# BattleBits_V4.net
KiCad netlist of a schematic drawn in EAGLE
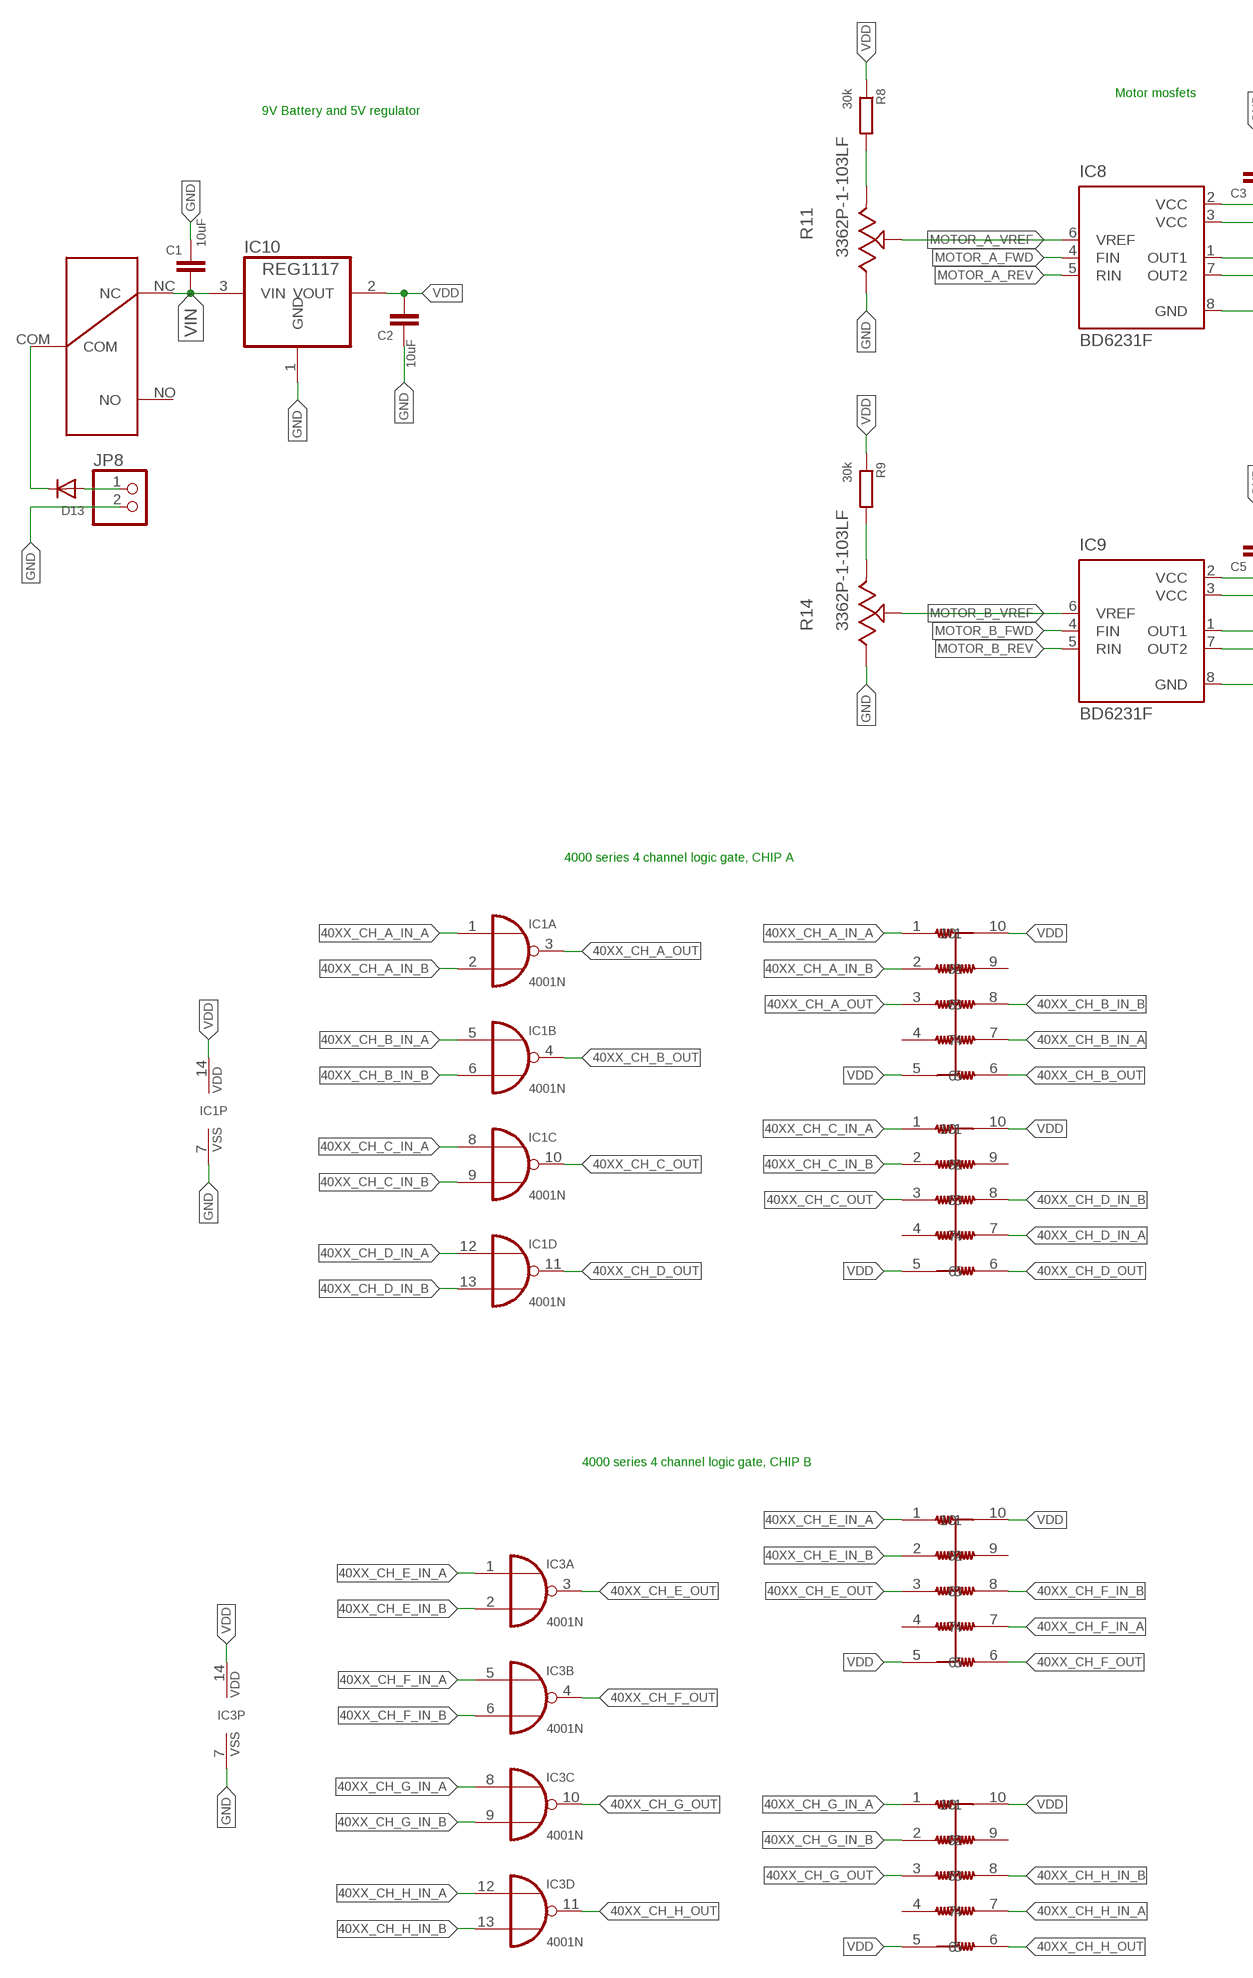
[diagram p0: schematic, sheet 1, part 1 of 2]
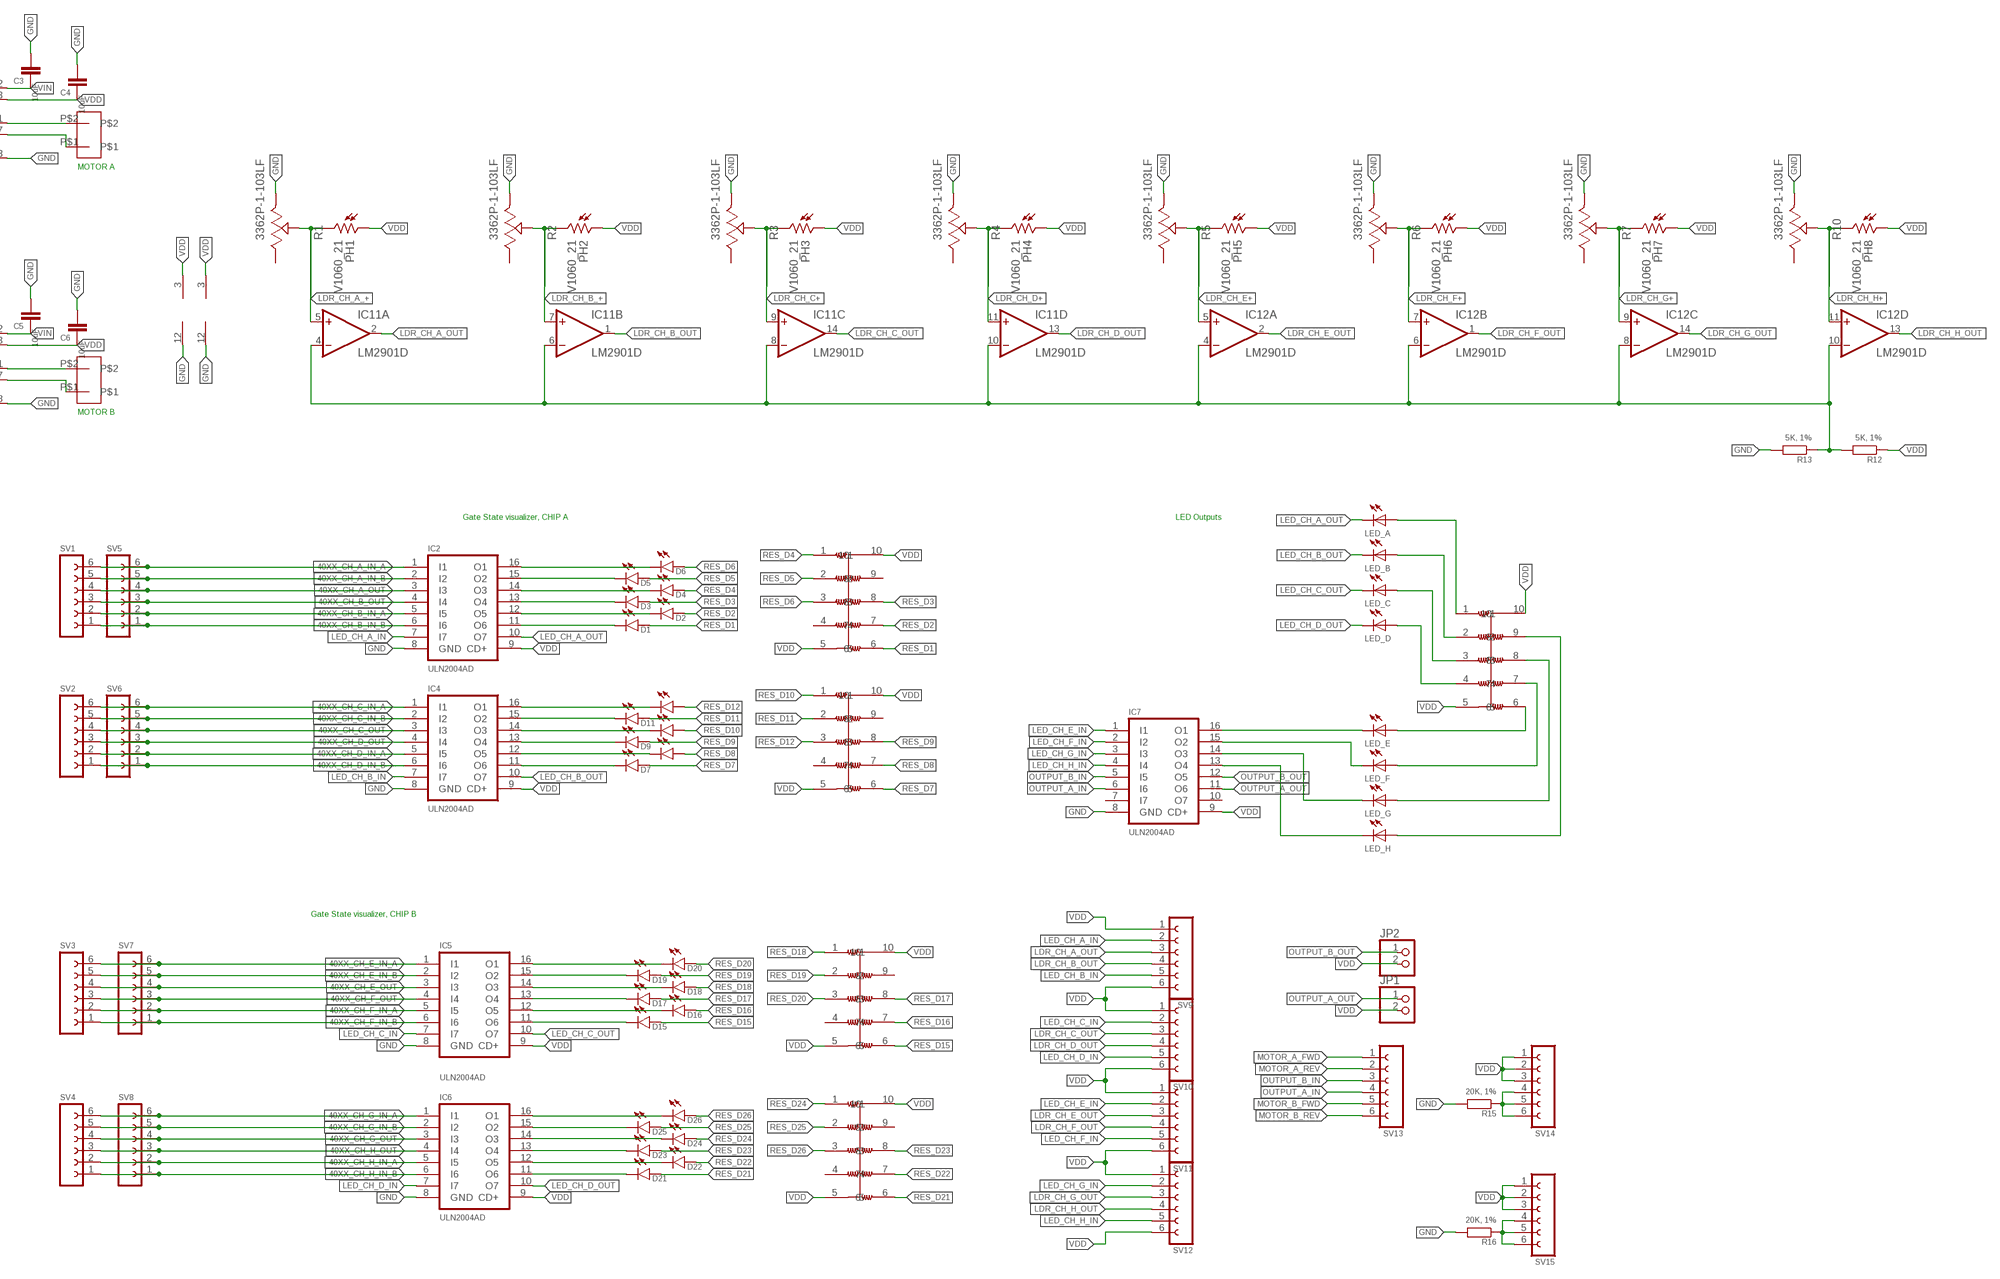
[diagram p1: schematic, sheet 1, part 2 of 2]

(export (version "E")
  (design (tool "Eeschema 10.0.6"))
  (components
    (comp (ref "C1")
      (value "10uF")
      (footprint "eagle-import:C3216")
      (libsource (lib "eagle-import") (part "C-EUC3216"))
    )
    (comp (ref "C2")
      (value "10uF")
      (footprint "eagle-import:C3216")
      (libsource (lib "eagle-import") (part "C-EUC3216"))
    )
    (comp (ref "C3")
      (value "10uF")
      (footprint "eagle-import:C3216")
      (libsource (lib "eagle-import") (part "C-EUC3216"))
    )
    (comp (ref "C4")
      (value "10uF")
      (footprint "eagle-import:C3216")
      (libsource (lib "eagle-import") (part "C-EUC3216"))
    )
    (comp (ref "C5")
      (value "10uF")
      (footprint "eagle-import:C3216")
      (libsource (lib "eagle-import") (part "C-EUC3216"))
    )
    (comp (ref "C6")
      (value "10uF")
      (footprint "eagle-import:C3216")
      (libsource (lib "eagle-import") (part "C-EUC3216"))
    )
    (comp (ref "D1")
      (value "LED1206")
      (footprint "eagle-import:LED-1206")
      (libsource (lib "eagle-import") (part "LED1206"))
    )
    (comp (ref "D2")
      (value "LED1206")
      (footprint "eagle-import:LED-1206")
      (libsource (lib "eagle-import") (part "LED1206"))
    )
    (comp (ref "D3")
      (value "LED1206")
      (footprint "eagle-import:LED-1206")
      (libsource (lib "eagle-import") (part "LED1206"))
    )
    (comp (ref "D4")
      (value "LED1206")
      (footprint "eagle-import:LED-1206")
      (libsource (lib "eagle-import") (part "LED1206"))
    )
    (comp (ref "D5")
      (value "LED1206")
      (footprint "eagle-import:LED-1206")
      (libsource (lib "eagle-import") (part "LED1206"))
    )
    (comp (ref "D6")
      (value "LED1206")
      (footprint "eagle-import:LED-1206")
      (libsource (lib "eagle-import") (part "LED1206"))
    )
    (comp (ref "D7")
      (value "LED1206")
      (footprint "eagle-import:LED-1206")
      (libsource (lib "eagle-import") (part "LED1206"))
    )
    (comp (ref "D8")
      (value "LED1206")
      (footprint "eagle-import:LED-1206")
      (libsource (lib "eagle-import") (part "LED1206"))
    )
    (comp (ref "D9")
      (value "LED1206")
      (footprint "eagle-import:LED-1206")
      (libsource (lib "eagle-import") (part "LED1206"))
    )
    (comp (ref "D10")
      (value "LED1206")
      (footprint "eagle-import:LED-1206")
      (libsource (lib "eagle-import") (part "LED1206"))
    )
    (comp (ref "D11")
      (value "LED1206")
      (footprint "eagle-import:LED-1206")
      (libsource (lib "eagle-import") (part "LED1206"))
    )
    (comp (ref "D12")
      (value "LED1206")
      (footprint "eagle-import:LED-1206")
      (libsource (lib "eagle-import") (part "LED1206"))
    )
    (comp (ref "D13")
      (value "DIODESMA")
      (footprint "eagle-import:SMADIODE")
      (libsource (lib "eagle-import") (part "DIODESMA"))
    )
    (comp (ref "D15")
      (value "LED1206")
      (footprint "eagle-import:LED-1206")
      (libsource (lib "eagle-import") (part "LED1206"))
    )
    (comp (ref "D16")
      (value "LED1206")
      (footprint "eagle-import:LED-1206")
      (libsource (lib "eagle-import") (part "LED1206"))
    )
    (comp (ref "D17")
      (value "LED1206")
      (footprint "eagle-import:LED-1206")
      (libsource (lib "eagle-import") (part "LED1206"))
    )
    (comp (ref "D18")
      (value "LED1206")
      (footprint "eagle-import:LED-1206")
      (libsource (lib "eagle-import") (part "LED1206"))
    )
    (comp (ref "D19")
      (value "LED1206")
      (footprint "eagle-import:LED-1206")
      (libsource (lib "eagle-import") (part "LED1206"))
    )
    (comp (ref "D20")
      (value "LED1206")
      (footprint "eagle-import:LED-1206")
      (libsource (lib "eagle-import") (part "LED1206"))
    )
    (comp (ref "D21")
      (value "LED1206")
      (footprint "eagle-import:LED-1206")
      (libsource (lib "eagle-import") (part "LED1206"))
    )
    (comp (ref "D22")
      (value "LED1206")
      (footprint "eagle-import:LED-1206")
      (libsource (lib "eagle-import") (part "LED1206"))
    )
    (comp (ref "D23")
      (value "LED1206")
      (footprint "eagle-import:LED-1206")
      (libsource (lib "eagle-import") (part "LED1206"))
    )
    (comp (ref "D24")
      (value "LED1206")
      (footprint "eagle-import:LED-1206")
      (libsource (lib "eagle-import") (part "LED1206"))
    )
    (comp (ref "D25")
      (value "LED1206")
      (footprint "eagle-import:LED-1206")
      (libsource (lib "eagle-import") (part "LED1206"))
    )
    (comp (ref "D26")
      (value "LED1206")
      (footprint "eagle-import:LED-1206")
      (libsource (lib "eagle-import") (part "LED1206"))
    )
    (comp (ref "IC1")
      (value "4001N")
      (footprint "eagle-import:DIL14")
      (libsource (lib "eagle-import") (part "4001N"))
    )
    (comp (ref "IC2")
      (value "ULN2004AD")
      (footprint "eagle-import:SO16")
      (libsource (lib "eagle-import") (part "ULN2004AD"))
    )
    (comp (ref "IC3")
      (value "4001N")
      (footprint "eagle-import:DIL14")
      (libsource (lib "eagle-import") (part "4001N"))
    )
    (comp (ref "IC4")
      (value "ULN2004AD")
      (footprint "eagle-import:SO16")
      (libsource (lib "eagle-import") (part "ULN2004AD"))
    )
    (comp (ref "IC5")
      (value "ULN2004AD")
      (footprint "eagle-import:SO16")
      (libsource (lib "eagle-import") (part "ULN2004AD"))
    )
    (comp (ref "IC6")
      (value "ULN2004AD")
      (footprint "eagle-import:SO16")
      (libsource (lib "eagle-import") (part "ULN2004AD"))
    )
    (comp (ref "IC7")
      (value "ULN2004AD")
      (footprint "eagle-import:SO16")
      (libsource (lib "eagle-import") (part "ULN2004AD"))
    )
    (comp (ref "IC8")
      (value "BD6231F")
      (footprint "eagle-import:SOP8")
      (fields (field (name "MPN") "BD6231F-E2"))
      (libsource (lib "eagle-import") (part "BD623F1"))
    )
    (comp (ref "IC9")
      (value "BD6231F")
      (footprint "eagle-import:SOP8")
      (fields (field (name "MPN") "BD6231F-E2"))
      (libsource (lib "eagle-import") (part "BD623F1"))
    )
    (comp (ref "IC10")
      (value "REG1117")
      (footprint "eagle-import:SOT223")
      (libsource (lib "eagle-import") (part "REG1117"))
    )
    (comp (ref "IC11")
      (value "LM2901D")
      (footprint "eagle-import:SO14")
      (libsource (lib "eagle-import") (part "LM2901D"))
    )
    (comp (ref "IC12")
      (value "LM2901D")
      (footprint "eagle-import:SO14")
      (libsource (lib "eagle-import") (part "LM2901D"))
    )
    (comp (ref "JP1")
      (value "PINHD-1X2")
      (footprint "eagle-import:1X02")
      (libsource (lib "eagle-import") (part "PINHD-1X2"))
    )
    (comp (ref "JP2")
      (value "PINHD-1X2")
      (footprint "eagle-import:1X02")
      (libsource (lib "eagle-import") (part "PINHD-1X2"))
    )
    (comp (ref "JP8")
      (value "PINHD-1X2")
      (footprint "eagle-import:1X02")
      (libsource (lib "eagle-import") (part "PINHD-1X2"))
    )
    (comp (ref "LED_A")
      (value "LED5MM")
      (footprint "eagle-import:LED5MM")
      (libsource (lib "eagle-import") (part "adafruit_420_LED5MM"))
    )
    (comp (ref "LED_B")
      (value "LED5MM")
      (footprint "eagle-import:LED5MM")
      (libsource (lib "eagle-import") (part "adafruit_420_LED5MM"))
    )
    (comp (ref "LED_C")
      (value "LED5MM")
      (footprint "eagle-import:LED5MM")
      (libsource (lib "eagle-import") (part "adafruit_420_LED5MM"))
    )
    (comp (ref "LED_D")
      (value "LED5MM")
      (footprint "eagle-import:LED5MM")
      (libsource (lib "eagle-import") (part "adafruit_420_LED5MM"))
    )
    (comp (ref "LED_E")
      (value "LED5MM")
      (footprint "eagle-import:LED5MM")
      (libsource (lib "eagle-import") (part "adafruit_420_LED5MM"))
    )
    (comp (ref "LED_F")
      (value "LED5MM")
      (footprint "eagle-import:LED5MM")
      (libsource (lib "eagle-import") (part "adafruit_420_LED5MM"))
    )
    (comp (ref "LED_G")
      (value "LED5MM")
      (footprint "eagle-import:LED5MM")
      (libsource (lib "eagle-import") (part "adafruit_420_LED5MM"))
    )
    (comp (ref "LED_H")
      (value "LED5MM")
      (footprint "eagle-import:LED5MM")
      (libsource (lib "eagle-import") (part "adafruit_420_LED5MM"))
    )
    (comp (ref "PH1")
      (value "V1060_21")
      (footprint "eagle-import:TO-5_V10")
      (libsource (lib "eagle-import") (part "?1060V_21"))
    )
    (comp (ref "PH2")
      (value "V1060_21")
      (footprint "eagle-import:TO-5_V10")
      (libsource (lib "eagle-import") (part "?1060V_21"))
    )
    (comp (ref "PH3")
      (value "V1060_21")
      (footprint "eagle-import:TO-5_V10")
      (libsource (lib "eagle-import") (part "?1060V_21"))
    )
    (comp (ref "PH4")
      (value "V1060_21")
      (footprint "eagle-import:TO-5_V10")
      (libsource (lib "eagle-import") (part "?1060V_21"))
    )
    (comp (ref "PH5")
      (value "V1060_21")
      (footprint "eagle-import:TO-5_V10")
      (libsource (lib "eagle-import") (part "?1060V_21"))
    )
    (comp (ref "PH6")
      (value "V1060_21")
      (footprint "eagle-import:TO-5_V10")
      (libsource (lib "eagle-import") (part "?1060V_21"))
    )
    (comp (ref "PH7")
      (value "V1060_21")
      (footprint "eagle-import:TO-5_V10")
      (libsource (lib "eagle-import") (part "?1060V_21"))
    )
    (comp (ref "PH8")
      (value "V1060_21")
      (footprint "eagle-import:TO-5_V10")
      (libsource (lib "eagle-import") (part "?1060V_21"))
    )
    (comp (ref "R1")
      (value "3362P-1-103LF")
      (footprint "eagle-import:3362P-1-103LF")
      (fields (field (name "MANUFACTURER") "Bourns Inc.") (field (name "CREATED_PN") "PCBLayout.com"))
      (libsource (lib "eagle-import") (part "3362P-1-103LF"))
    )
    (comp (ref "R2")
      (value "3362P-1-103LF")
      (footprint "eagle-import:3362P-1-103LF")
      (fields (field (name "MANUFACTURER") "Bourns Inc.") (field (name "CREATED_PN") "PCBLayout.com"))
      (libsource (lib "eagle-import") (part "3362P-1-103LF"))
    )
    (comp (ref "R3")
      (value "3362P-1-103LF")
      (footprint "eagle-import:3362P-1-103LF")
      (fields (field (name "MANUFACTURER") "Bourns Inc.") (field (name "CREATED_PN") "PCBLayout.com"))
      (libsource (lib "eagle-import") (part "3362P-1-103LF"))
    )
    (comp (ref "R4")
      (value "3362P-1-103LF")
      (footprint "eagle-import:3362P-1-103LF")
      (fields (field (name "MANUFACTURER") "Bourns Inc.") (field (name "CREATED_PN") "PCBLayout.com"))
      (libsource (lib "eagle-import") (part "3362P-1-103LF"))
    )
    (comp (ref "R5")
      (value "3362P-1-103LF")
      (footprint "eagle-import:3362P-1-103LF")
      (fields (field (name "MANUFACTURER") "Bourns Inc.") (field (name "CREATED_PN") "PCBLayout.com"))
      (libsource (lib "eagle-import") (part "3362P-1-103LF"))
    )
    (comp (ref "R6")
      (value "3362P-1-103LF")
      (footprint "eagle-import:3362P-1-103LF")
      (fields (field (name "MANUFACTURER") "Bourns Inc.") (field (name "CREATED_PN") "PCBLayout.com"))
      (libsource (lib "eagle-import") (part "3362P-1-103LF"))
    )
    (comp (ref "R7")
      (value "3362P-1-103LF")
      (footprint "eagle-import:3362P-1-103LF")
      (fields (field (name "MANUFACTURER") "Bourns Inc.") (field (name "CREATED_PN") "PCBLayout.com"))
      (libsource (lib "eagle-import") (part "3362P-1-103LF"))
    )
    (comp (ref "R8")
      (value "30k")
      (footprint "eagle-import:R3216")
      (libsource (lib "eagle-import") (part "R-EU_R3216"))
    )
    (comp (ref "R9")
      (value "30k")
      (footprint "eagle-import:R3216")
      (libsource (lib "eagle-import") (part "R-EU_R3216"))
    )
    (comp (ref "R10")
      (value "3362P-1-103LF")
      (footprint "eagle-import:3362P-1-103LF")
      (fields (field (name "MANUFACTURER") "Bourns Inc.") (field (name "CREATED_PN") "PCBLayout.com"))
      (libsource (lib "eagle-import") (part "3362P-1-103LF"))
    )
    (comp (ref "R11")
      (value "3362P-1-103LF")
      (footprint "eagle-import:3362P-1-103LF")
      (fields (field (name "MANUFACTURER") "Bourns Inc.") (field (name "CREATED_PN") "PCBLayout.com"))
      (libsource (lib "eagle-import") (part "3362P-1-103LF"))
    )
    (comp (ref "R12")
      (value "5K, 1%")
      (footprint "eagle-import:R3216")
      (libsource (lib "eagle-import") (part "R-EU_R3216"))
    )
    (comp (ref "R13")
      (value "5K, 1%")
      (footprint "eagle-import:R3216")
      (libsource (lib "eagle-import") (part "R-EU_R3216"))
    )
    (comp (ref "R14")
      (value "3362P-1-103LF")
      (footprint "eagle-import:3362P-1-103LF")
      (fields (field (name "MANUFACTURER") "Bourns Inc.") (field (name "CREATED_PN") "PCBLayout.com"))
      (libsource (lib "eagle-import") (part "3362P-1-103LF"))
    )
    (comp (ref "R15")
      (value "20K, 1%")
      (footprint "eagle-import:R3216")
      (libsource (lib "eagle-import") (part "R-EU_R3216"))
    )
    (comp (ref "R16")
      (value "20K, 1%")
      (footprint "eagle-import:R3216")
      (libsource (lib "eagle-import") (part "R-EU_R3216"))
    )
    (comp (ref "SV1")
      (value "FE06-1")
      (footprint "eagle-import:FE06")
      (libsource (lib "eagle-import") (part "FE06-1"))
    )
    (comp (ref "SV2")
      (value "FE06-1")
      (footprint "eagle-import:FE06")
      (libsource (lib "eagle-import") (part "FE06-1"))
    )
    (comp (ref "SV3")
      (value "FE06-1")
      (footprint "eagle-import:FE06")
      (libsource (lib "eagle-import") (part "FE06-1"))
    )
    (comp (ref "SV4")
      (value "FE06-1")
      (footprint "eagle-import:FE06")
      (libsource (lib "eagle-import") (part "FE06-1"))
    )
    (comp (ref "SV5")
      (value "FE06-1")
      (footprint "eagle-import:FE06")
      (libsource (lib "eagle-import") (part "FE06-1"))
    )
    (comp (ref "SV6")
      (value "FE06-1")
      (footprint "eagle-import:FE06")
      (libsource (lib "eagle-import") (part "FE06-1"))
    )
    (comp (ref "SV7")
      (value "FE06-1")
      (footprint "eagle-import:FE06")
      (libsource (lib "eagle-import") (part "FE06-1"))
    )
    (comp (ref "SV8")
      (value "FE06-1")
      (footprint "eagle-import:FE06")
      (libsource (lib "eagle-import") (part "FE06-1"))
    )
    (comp (ref "SV9")
      (value "FE06-1")
      (footprint "eagle-import:FE06")
      (libsource (lib "eagle-import") (part "FE06-1"))
    )
    (comp (ref "SV10")
      (value "FE06-1")
      (footprint "eagle-import:FE06")
      (libsource (lib "eagle-import") (part "FE06-1"))
    )
    (comp (ref "SV11")
      (value "FE06-1")
      (footprint "eagle-import:FE06")
      (libsource (lib "eagle-import") (part "FE06-1"))
    )
    (comp (ref "SV12")
      (value "FE06-1")
      (footprint "eagle-import:FE06")
      (libsource (lib "eagle-import") (part "FE06-1"))
    )
    (comp (ref "SV13")
      (value "FE06-1")
      (footprint "eagle-import:FE06")
      (libsource (lib "eagle-import") (part "FE06-1"))
    )
    (comp (ref "SV14")
      (value "FE06-1")
      (footprint "eagle-import:FE06")
      (libsource (lib "eagle-import") (part "FE06-1"))
    )
    (comp (ref "SV15")
      (value "FE06-1")
      (footprint "eagle-import:FE06")
      (libsource (lib "eagle-import") (part "FE06-1"))
    )
    (comp (ref "U$1")
      (value "MOTOR")
      (footprint "eagle-import:GEARMOTOR")
      (libsource (lib "eagle-import") (part "MOTOR"))
    )
    (comp (ref "U$2")
      (value "MOTOR")
      (footprint "eagle-import:GEARMOTOR")
      (libsource (lib "eagle-import") (part "MOTOR"))
    )
    (comp (ref "U$3")
      (value "10K")
      (footprint "eagle-import:EXBA")
      (libsource (lib "eagle-import") (part "EXBA_10P"))
    )
    (comp (ref "U$4")
      (value "330")
      (footprint "eagle-import:EXBA")
      (libsource (lib "eagle-import") (part "EXBA_10P"))
    )
    (comp (ref "U$5")
      (value "10K")
      (footprint "eagle-import:EXBA")
      (libsource (lib "eagle-import") (part "EXBA_10P"))
    )
    (comp (ref "U$6")
      (value "10K")
      (footprint "eagle-import:EXBA")
      (libsource (lib "eagle-import") (part "EXBA_10P"))
    )
    (comp (ref "U$7")
      (value "SLIDE_SWITCH")
      (footprint "eagle-import:SLIDE_SWITCH")
      (libsource (lib "eagle-import") (part "SLIDE_SWITCH"))
    )
    (comp (ref "U$9")
      (value "10K")
      (footprint "eagle-import:EXBA")
      (libsource (lib "eagle-import") (part "EXBA_10P"))
    )
    (comp (ref "U$10")
      (value "10K")
      (footprint "eagle-import:EXBA")
      (libsource (lib "eagle-import") (part "EXBA_10P"))
    )
    (comp (ref "U$11")
      (value "10K")
      (footprint "eagle-import:EXBA")
      (libsource (lib "eagle-import") (part "EXBA_10P"))
    )
    (comp (ref "U$19")
      (value "10K")
      (footprint "eagle-import:EXBA")
      (libsource (lib "eagle-import") (part "EXBA_10P"))
    )
    (comp (ref "U$20")
      (value "10K")
      (footprint "eagle-import:EXBA")
      (libsource (lib "eagle-import") (part "EXBA_10P"))
    )
  )
  (nets
    (net (code "1") (name "40XX_CH_A_IN_A") (class "Default")
      (node (ref "IC1") (pin "1") (pinfunction "I0_1") (pintype "input"))
      (node (ref "IC2") (pin "1") (pinfunction "I1_1") (pintype "input"))
      (node (ref "SV1") (pin "6") (pinfunction "6_6") (pintype "passive"))
      (node (ref "SV5") (pin "6") (pinfunction "6_6") (pintype "passive"))
      (node (ref "U$3") (pin "1") (pinfunction "1_1") (pintype "bidirectional"))
    )
    (net (code "2") (name "40XX_CH_A_IN_B") (class "Default")
      (node (ref "IC1") (pin "2") (pinfunction "I1_2") (pintype "input"))
      (node (ref "IC2") (pin "2") (pinfunction "I2_2") (pintype "input"))
      (node (ref "SV1") (pin "5") (pinfunction "5_5") (pintype "passive"))
      (node (ref "SV5") (pin "5") (pinfunction "5_5") (pintype "passive"))
      (node (ref "U$3") (pin "2") (pinfunction "2_2") (pintype "bidirectional"))
    )
    (net (code "3") (name "40XX_CH_A_OUT") (class "Default")
      (node (ref "IC1") (pin "3") (pinfunction "O_3") (pintype "output"))
      (node (ref "IC2") (pin "3") (pinfunction "I3_3") (pintype "input"))
      (node (ref "SV1") (pin "4") (pinfunction "4_4") (pintype "passive"))
      (node (ref "SV5") (pin "4") (pinfunction "4_4") (pintype "passive"))
      (node (ref "U$3") (pin "3") (pinfunction "3_3") (pintype "bidirectional"))
    )
    (net (code "4") (name "40XX_CH_B_IN_A") (class "Default")
      (node (ref "IC1") (pin "5") (pinfunction "I0_5") (pintype "input"))
      (node (ref "IC2") (pin "5") (pinfunction "I5_5") (pintype "input"))
      (node (ref "SV1") (pin "2") (pinfunction "2_2") (pintype "passive"))
      (node (ref "SV5") (pin "2") (pinfunction "2_2") (pintype "passive"))
      (node (ref "U$3") (pin "7") (pinfunction "7_7") (pintype "bidirectional"))
    )
    (net (code "5") (name "40XX_CH_B_IN_B") (class "Default")
      (node (ref "IC1") (pin "6") (pinfunction "I1_6") (pintype "input"))
      (node (ref "IC2") (pin "6") (pinfunction "I6_6") (pintype "input"))
      (node (ref "SV1") (pin "1") (pinfunction "1_1") (pintype "passive"))
      (node (ref "SV5") (pin "1") (pinfunction "1_1") (pintype "passive"))
      (node (ref "U$3") (pin "8") (pinfunction "8_8") (pintype "bidirectional"))
    )
    (net (code "6") (name "40XX_CH_B_OUT") (class "Default")
      (node (ref "IC1") (pin "4") (pinfunction "O_4") (pintype "output"))
      (node (ref "IC2") (pin "4") (pinfunction "I4_4") (pintype "input"))
      (node (ref "SV1") (pin "3") (pinfunction "3_3") (pintype "passive"))
      (node (ref "SV5") (pin "3") (pinfunction "3_3") (pintype "passive"))
      (node (ref "U$3") (pin "6") (pinfunction "6_6") (pintype "bidirectional"))
    )
    (net (code "7") (name "40XX_CH_C_IN_A") (class "Default")
      (node (ref "IC1") (pin "8") (pinfunction "I0_8") (pintype "input"))
      (node (ref "IC4") (pin "1") (pinfunction "I1_1") (pintype "input"))
      (node (ref "SV2") (pin "6") (pinfunction "6_6") (pintype "passive"))
      (node (ref "SV6") (pin "6") (pinfunction "6_6") (pintype "passive"))
      (node (ref "U$10") (pin "1") (pinfunction "1_1") (pintype "bidirectional"))
    )
    (net (code "8") (name "40XX_CH_C_IN_B") (class "Default")
      (node (ref "IC1") (pin "9") (pinfunction "I1_9") (pintype "input"))
      (node (ref "IC4") (pin "2") (pinfunction "I2_2") (pintype "input"))
      (node (ref "SV2") (pin "5") (pinfunction "5_5") (pintype "passive"))
      (node (ref "SV6") (pin "5") (pinfunction "5_5") (pintype "passive"))
      (node (ref "U$10") (pin "2") (pinfunction "2_2") (pintype "bidirectional"))
    )
    (net (code "9") (name "40XX_CH_C_OUT") (class "Default")
      (node (ref "IC1") (pin "10") (pinfunction "O_10") (pintype "output"))
      (node (ref "IC4") (pin "3") (pinfunction "I3_3") (pintype "input"))
      (node (ref "SV2") (pin "4") (pinfunction "4_4") (pintype "passive"))
      (node (ref "SV6") (pin "4") (pinfunction "4_4") (pintype "passive"))
      (node (ref "U$10") (pin "3") (pinfunction "3_3") (pintype "bidirectional"))
    )
    (net (code "10") (name "40XX_CH_D_IN_A") (class "Default")
      (node (ref "IC1") (pin "12") (pinfunction "I0_12") (pintype "input"))
      (node (ref "IC4") (pin "5") (pinfunction "I5_5") (pintype "input"))
      (node (ref "SV2") (pin "2") (pinfunction "2_2") (pintype "passive"))
      (node (ref "SV6") (pin "2") (pinfunction "2_2") (pintype "passive"))
      (node (ref "U$10") (pin "7") (pinfunction "7_7") (pintype "bidirectional"))
    )
    (net (code "11") (name "40XX_CH_D_IN_B") (class "Default")
      (node (ref "IC1") (pin "13") (pinfunction "I1_13") (pintype "input"))
      (node (ref "IC4") (pin "6") (pinfunction "I6_6") (pintype "input"))
      (node (ref "SV2") (pin "1") (pinfunction "1_1") (pintype "passive"))
      (node (ref "SV6") (pin "1") (pinfunction "1_1") (pintype "passive"))
      (node (ref "U$10") (pin "8") (pinfunction "8_8") (pintype "bidirectional"))
    )
    (net (code "12") (name "40XX_CH_D_OUT") (class "Default")
      (node (ref "IC1") (pin "11") (pinfunction "O_11") (pintype "output"))
      (node (ref "IC4") (pin "4") (pinfunction "I4_4") (pintype "input"))
      (node (ref "SV2") (pin "3") (pinfunction "3_3") (pintype "passive"))
      (node (ref "SV6") (pin "3") (pinfunction "3_3") (pintype "passive"))
      (node (ref "U$10") (pin "6") (pinfunction "6_6") (pintype "bidirectional"))
    )
    (net (code "13") (name "40XX_CH_E_IN_A") (class "Default")
      (node (ref "IC3") (pin "1") (pinfunction "I0_1") (pintype "input"))
      (node (ref "IC5") (pin "1") (pinfunction "I1_1") (pintype "input"))
      (node (ref "SV3") (pin "6") (pinfunction "6_6") (pintype "passive"))
      (node (ref "SV7") (pin "6") (pinfunction "6_6") (pintype "passive"))
      (node (ref "U$11") (pin "1") (pinfunction "1_1") (pintype "bidirectional"))
    )
    (net (code "14") (name "40XX_CH_E_IN_B") (class "Default")
      (node (ref "IC3") (pin "2") (pinfunction "I1_2") (pintype "input"))
      (node (ref "IC5") (pin "2") (pinfunction "I2_2") (pintype "input"))
      (node (ref "SV3") (pin "5") (pinfunction "5_5") (pintype "passive"))
      (node (ref "SV7") (pin "5") (pinfunction "5_5") (pintype "passive"))
      (node (ref "U$11") (pin "2") (pinfunction "2_2") (pintype "bidirectional"))
    )
    (net (code "15") (name "40XX_CH_E_OUT") (class "Default")
      (node (ref "IC3") (pin "3") (pinfunction "O_3") (pintype "output"))
      (node (ref "IC5") (pin "3") (pinfunction "I3_3") (pintype "input"))
      (node (ref "SV3") (pin "4") (pinfunction "4_4") (pintype "passive"))
      (node (ref "SV7") (pin "4") (pinfunction "4_4") (pintype "passive"))
      (node (ref "U$11") (pin "3") (pinfunction "3_3") (pintype "bidirectional"))
    )
    (net (code "16") (name "40XX_CH_F_IN_A") (class "Default")
      (node (ref "IC3") (pin "5") (pinfunction "I0_5") (pintype "input"))
      (node (ref "IC5") (pin "5") (pinfunction "I5_5") (pintype "input"))
      (node (ref "SV3") (pin "2") (pinfunction "2_2") (pintype "passive"))
      (node (ref "SV7") (pin "2") (pinfunction "2_2") (pintype "passive"))
      (node (ref "U$11") (pin "7") (pinfunction "7_7") (pintype "bidirectional"))
    )
    (net (code "17") (name "40XX_CH_F_IN_B") (class "Default")
      (node (ref "IC3") (pin "6") (pinfunction "I1_6") (pintype "input"))
      (node (ref "IC5") (pin "6") (pinfunction "I6_6") (pintype "input"))
      (node (ref "SV3") (pin "1") (pinfunction "1_1") (pintype "passive"))
      (node (ref "SV7") (pin "1") (pinfunction "1_1") (pintype "passive"))
      (node (ref "U$11") (pin "8") (pinfunction "8_8") (pintype "bidirectional"))
    )
    (net (code "18") (name "40XX_CH_F_OUT") (class "Default")
      (node (ref "IC3") (pin "4") (pinfunction "O_4") (pintype "output"))
      (node (ref "IC5") (pin "4") (pinfunction "I4_4") (pintype "input"))
      (node (ref "SV3") (pin "3") (pinfunction "3_3") (pintype "passive"))
      (node (ref "SV7") (pin "3") (pinfunction "3_3") (pintype "passive"))
      (node (ref "U$11") (pin "6") (pinfunction "6_6") (pintype "bidirectional"))
    )
    (net (code "19") (name "40XX_CH_G_IN_A") (class "Default")
      (node (ref "IC3") (pin "8") (pinfunction "I0_8") (pintype "input"))
      (node (ref "IC6") (pin "1") (pinfunction "I1_1") (pintype "input"))
      (node (ref "SV4") (pin "6") (pinfunction "6_6") (pintype "passive"))
      (node (ref "SV8") (pin "6") (pinfunction "6_6") (pintype "passive"))
      (node (ref "U$20") (pin "1") (pinfunction "1_1") (pintype "bidirectional"))
    )
    (net (code "20") (name "40XX_CH_G_IN_B") (class "Default")
      (node (ref "IC3") (pin "9") (pinfunction "I1_9") (pintype "input"))
      (node (ref "IC6") (pin "2") (pinfunction "I2_2") (pintype "input"))
      (node (ref "SV4") (pin "5") (pinfunction "5_5") (pintype "passive"))
      (node (ref "SV8") (pin "5") (pinfunction "5_5") (pintype "passive"))
      (node (ref "U$20") (pin "2") (pinfunction "2_2") (pintype "bidirectional"))
    )
    (net (code "21") (name "40XX_CH_G_OUT") (class "Default")
      (node (ref "IC3") (pin "10") (pinfunction "O_10") (pintype "output"))
      (node (ref "IC6") (pin "3") (pinfunction "I3_3") (pintype "input"))
      (node (ref "SV4") (pin "4") (pinfunction "4_4") (pintype "passive"))
      (node (ref "SV8") (pin "4") (pinfunction "4_4") (pintype "passive"))
      (node (ref "U$20") (pin "3") (pinfunction "3_3") (pintype "bidirectional"))
    )
    (net (code "22") (name "40XX_CH_H_IN_A") (class "Default")
      (node (ref "IC3") (pin "12") (pinfunction "I0_12") (pintype "input"))
      (node (ref "IC6") (pin "5") (pinfunction "I5_5") (pintype "input"))
      (node (ref "SV4") (pin "2") (pinfunction "2_2") (pintype "passive"))
      (node (ref "SV8") (pin "2") (pinfunction "2_2") (pintype "passive"))
      (node (ref "U$20") (pin "7") (pinfunction "7_7") (pintype "bidirectional"))
    )
    (net (code "23") (name "40XX_CH_H_IN_B") (class "Default")
      (node (ref "IC3") (pin "13") (pinfunction "I1_13") (pintype "input"))
      (node (ref "IC6") (pin "6") (pinfunction "I6_6") (pintype "input"))
      (node (ref "SV4") (pin "1") (pinfunction "1_1") (pintype "passive"))
      (node (ref "SV8") (pin "1") (pinfunction "1_1") (pintype "passive"))
      (node (ref "U$20") (pin "8") (pinfunction "8_8") (pintype "bidirectional"))
    )
    (net (code "24") (name "40XX_CH_H_OUT") (class "Default")
      (node (ref "IC3") (pin "11") (pinfunction "O_11") (pintype "output"))
      (node (ref "IC6") (pin "4") (pinfunction "I4_4") (pintype "input"))
      (node (ref "SV4") (pin "3") (pinfunction "3_3") (pintype "passive"))
      (node (ref "SV8") (pin "3") (pinfunction "3_3") (pintype "passive"))
      (node (ref "U$20") (pin "6") (pinfunction "6_6") (pintype "bidirectional"))
    )
    (net (code "25") (name "GND") (class "Default")
      (node (ref "C1") (pin "1") (pinfunction "1_1") (pintype "passive"))
      (node (ref "C2") (pin "1") (pinfunction "1_1") (pintype "passive"))
      (node (ref "C3") (pin "2") (pinfunction "2_2") (pintype "passive"))
      (node (ref "C4") (pin "2") (pinfunction "2_2") (pintype "passive"))
      (node (ref "C5") (pin "2") (pinfunction "2_2") (pintype "passive"))
      (node (ref "C6") (pin "2") (pinfunction "2_2") (pintype "passive"))
      (node (ref "IC1") (pin "7") (pinfunction "VSS_7") (pintype "power_in"))
      (node (ref "IC10") (pin "1") (pinfunction "GND_1") (pintype "power_in"))
      (node (ref "IC11") (pin "12") (pinfunction "V-_12") (pintype "power_in"))
      (node (ref "IC12") (pin "12") (pinfunction "V-_12") (pintype "power_in"))
      (node (ref "IC2") (pin "8") (pinfunction "GND_8") (pintype "power_in"))
      (node (ref "IC3") (pin "7") (pinfunction "VSS_7") (pintype "power_in"))
      (node (ref "IC4") (pin "8") (pinfunction "GND_8") (pintype "power_in"))
      (node (ref "IC5") (pin "8") (pinfunction "GND_8") (pintype "power_in"))
      (node (ref "IC6") (pin "8") (pinfunction "GND_8") (pintype "power_in"))
      (node (ref "IC7") (pin "8") (pinfunction "GND_8") (pintype "power_in"))
      (node (ref "IC8") (pin "8") (pinfunction "GND_8") (pintype "power_in"))
      (node (ref "IC9") (pin "8") (pinfunction "GND_8") (pintype "power_in"))
      (node (ref "JP8") (pin "2") (pinfunction "2_2") (pintype "passive"))
      (node (ref "R1") (pin "1") (pinfunction "1_1") (pintype "passive"))
      (node (ref "R10") (pin "1") (pinfunction "1_1") (pintype "passive"))
      (node (ref "R11") (pin "3") (pinfunction "3_3") (pintype "passive"))
      (node (ref "R13") (pin "2") (pinfunction "2_2") (pintype "passive"))
      (node (ref "R14") (pin "3") (pinfunction "3_3") (pintype "passive"))
      (node (ref "R15") (pin "2") (pinfunction "2_2") (pintype "passive"))
      (node (ref "R16") (pin "2") (pinfunction "2_2") (pintype "passive"))
      (node (ref "R2") (pin "1") (pinfunction "1_1") (pintype "passive"))
      (node (ref "R3") (pin "1") (pinfunction "1_1") (pintype "passive"))
      (node (ref "R4") (pin "1") (pinfunction "1_1") (pintype "passive"))
      (node (ref "R5") (pin "1") (pinfunction "1_1") (pintype "passive"))
      (node (ref "R6") (pin "1") (pinfunction "1_1") (pintype "passive"))
      (node (ref "R7") (pin "1") (pinfunction "1_1") (pintype "passive"))
    )
    (net (code "26") (name "LDR_CH_A_+") (class "Default")
      (node (ref "IC11") (pin "5") (pinfunction "+IN_5") (pintype "input"))
      (node (ref "PH1") (pin "2") (pinfunction "2_2") (pintype "passive"))
      (node (ref "R1") (pin "2") (pinfunction "2_2") (pintype "passive"))
    )
    (net (code "27") (name "LDR_CH_A_OUT") (class "Default")
      (node (ref "IC11") (pin "2") (pinfunction "OUT_2") (pintype "output"))
      (node (ref "SV9") (pin "3") (pinfunction "3_3") (pintype "passive"))
    )
    (net (code "28") (name "LDR_CH_B_+") (class "Default")
      (node (ref "IC11") (pin "7") (pinfunction "+IN_7") (pintype "input"))
      (node (ref "PH2") (pin "2") (pinfunction "2_2") (pintype "passive"))
      (node (ref "R2") (pin "2") (pinfunction "2_2") (pintype "passive"))
    )
    (net (code "29") (name "LDR_CH_B_OUT") (class "Default")
      (node (ref "IC11") (pin "1") (pinfunction "OUT_1") (pintype "output"))
      (node (ref "SV9") (pin "4") (pinfunction "4_4") (pintype "passive"))
    )
    (net (code "30") (name "LDR_CH_C+") (class "Default")
      (node (ref "IC11") (pin "9") (pinfunction "+IN_9") (pintype "input"))
      (node (ref "PH3") (pin "2") (pinfunction "2_2") (pintype "passive"))
      (node (ref "R3") (pin "2") (pinfunction "2_2") (pintype "passive"))
    )
    (net (code "31") (name "LDR_CH_C_OUT") (class "Default")
      (node (ref "IC11") (pin "14") (pinfunction "OUT_14") (pintype "output"))
      (node (ref "SV10") (pin "3") (pinfunction "3_3") (pintype "passive"))
    )
    (net (code "32") (name "LDR_CH_D+") (class "Default")
      (node (ref "IC11") (pin "11") (pinfunction "+IN_11") (pintype "input"))
      (node (ref "PH4") (pin "2") (pinfunction "2_2") (pintype "passive"))
      (node (ref "R4") (pin "2") (pinfunction "2_2") (pintype "passive"))
    )
    (net (code "33") (name "LDR_CH_D_OUT") (class "Default")
      (node (ref "IC11") (pin "13") (pinfunction "OUT_13") (pintype "output"))
      (node (ref "SV10") (pin "4") (pinfunction "4_4") (pintype "passive"))
    )
    (net (code "34") (name "LDR_CH_E+") (class "Default")
      (node (ref "IC12") (pin "5") (pinfunction "+IN_5") (pintype "input"))
      (node (ref "PH5") (pin "2") (pinfunction "2_2") (pintype "passive"))
      (node (ref "R5") (pin "2") (pinfunction "2_2") (pintype "passive"))
    )
    (net (code "35") (name "LDR_CH_E_OUT") (class "Default")
      (node (ref "IC12") (pin "2") (pinfunction "OUT_2") (pintype "output"))
      (node (ref "SV11") (pin "3") (pinfunction "3_3") (pintype "passive"))
    )
    (net (code "36") (name "LDR_CH_F+") (class "Default")
      (node (ref "IC12") (pin "7") (pinfunction "+IN_7") (pintype "input"))
      (node (ref "PH6") (pin "2") (pinfunction "2_2") (pintype "passive"))
      (node (ref "R6") (pin "2") (pinfunction "2_2") (pintype "passive"))
    )
    (net (code "37") (name "LDR_CH_F_OUT") (class "Default")
      (node (ref "IC12") (pin "1") (pinfunction "OUT_1") (pintype "output"))
      (node (ref "SV11") (pin "4") (pinfunction "4_4") (pintype "passive"))
    )
    (net (code "38") (name "LDR_CH_G+") (class "Default")
      (node (ref "IC12") (pin "9") (pinfunction "+IN_9") (pintype "input"))
      (node (ref "PH7") (pin "2") (pinfunction "2_2") (pintype "passive"))
      (node (ref "R7") (pin "2") (pinfunction "2_2") (pintype "passive"))
    )
    (net (code "39") (name "LDR_CH_G_OUT") (class "Default")
      (node (ref "IC12") (pin "14") (pinfunction "OUT_14") (pintype "output"))
      (node (ref "SV12") (pin "3") (pinfunction "3_3") (pintype "passive"))
    )
    (net (code "40") (name "LDR_CH_H+") (class "Default")
      (node (ref "IC12") (pin "11") (pinfunction "+IN_11") (pintype "input"))
      (node (ref "PH8") (pin "2") (pinfunction "2_2") (pintype "passive"))
      (node (ref "R10") (pin "2") (pinfunction "2_2") (pintype "passive"))
    )
    (net (code "41") (name "LDR_CH_H_OUT") (class "Default")
      (node (ref "IC12") (pin "13") (pinfunction "OUT_13") (pintype "output"))
      (node (ref "SV12") (pin "4") (pinfunction "4_4") (pintype "passive"))
    )
    (net (code "42") (name "LED_CH_A_IN") (class "Default")
      (node (ref "IC2") (pin "7") (pinfunction "I7_7") (pintype "input"))
      (node (ref "SV9") (pin "2") (pinfunction "2_2") (pintype "passive"))
    )
    (net (code "43") (name "LED_CH_A_OUT") (class "Default")
      (node (ref "IC2") (pin "10") (pinfunction "O7_10") (pintype "open_collector"))
      (node (ref "LED_A") (pin "K") (pinfunction "C_K") (pintype "passive"))
    )
    (net (code "44") (name "LED_CH_B_IN") (class "Default")
      (node (ref "IC4") (pin "7") (pinfunction "I7_7") (pintype "input"))
      (node (ref "SV9") (pin "5") (pinfunction "5_5") (pintype "passive"))
    )
    (net (code "45") (name "LED_CH_B_OUT") (class "Default")
      (node (ref "IC4") (pin "10") (pinfunction "O7_10") (pintype "open_collector"))
      (node (ref "LED_B") (pin "K") (pinfunction "C_K") (pintype "passive"))
    )
    (net (code "46") (name "LED_CH_C_IN") (class "Default")
      (node (ref "IC5") (pin "7") (pinfunction "I7_7") (pintype "input"))
      (node (ref "SV10") (pin "2") (pinfunction "2_2") (pintype "passive"))
    )
    (net (code "47") (name "LED_CH_C_OUT") (class "Default")
      (node (ref "IC5") (pin "10") (pinfunction "O7_10") (pintype "open_collector"))
      (node (ref "LED_C") (pin "K") (pinfunction "C_K") (pintype "passive"))
    )
    (net (code "48") (name "LED_CH_D_IN") (class "Default")
      (node (ref "IC6") (pin "7") (pinfunction "I7_7") (pintype "input"))
      (node (ref "SV10") (pin "5") (pinfunction "5_5") (pintype "passive"))
    )
    (net (code "49") (name "LED_CH_D_OUT") (class "Default")
      (node (ref "IC6") (pin "10") (pinfunction "O7_10") (pintype "open_collector"))
      (node (ref "LED_D") (pin "K") (pinfunction "C_K") (pintype "passive"))
    )
    (net (code "50") (name "LED_CH_E_IN") (class "Default")
      (node (ref "IC7") (pin "1") (pinfunction "I1_1") (pintype "input"))
      (node (ref "SV11") (pin "2") (pinfunction "2_2") (pintype "passive"))
    )
    (net (code "51") (name "LED_CH_F_IN") (class "Default")
      (node (ref "IC7") (pin "2") (pinfunction "I2_2") (pintype "input"))
      (node (ref "SV11") (pin "5") (pinfunction "5_5") (pintype "passive"))
    )
    (net (code "52") (name "LED_CH_G_IN") (class "Default")
      (node (ref "IC7") (pin "3") (pinfunction "I3_3") (pintype "input"))
      (node (ref "SV12") (pin "2") (pinfunction "2_2") (pintype "passive"))
    )
    (net (code "53") (name "LED_CH_H_IN") (class "Default")
      (node (ref "IC7") (pin "4") (pinfunction "I4_4") (pintype "input"))
      (node (ref "SV12") (pin "5") (pinfunction "5_5") (pintype "passive"))
    )
    (net (code "54") (name "MOTOR_A_FWD") (class "Default")
      (node (ref "IC8") (pin "4") (pinfunction "FIN_4") (pintype "input"))
      (node (ref "SV13") (pin "1") (pinfunction "1_1") (pintype "passive"))
    )
    (net (code "55") (name "MOTOR_A_REV") (class "Default")
      (node (ref "IC8") (pin "5") (pinfunction "RIN_5") (pintype "input"))
      (node (ref "SV13") (pin "2") (pinfunction "2_2") (pintype "passive"))
    )
    (net (code "56") (name "MOTOR_A_VREF") (class "Default")
      (node (ref "IC8") (pin "6") (pinfunction "VREF_6") (pintype "passive"))
      (node (ref "R11") (pin "2") (pinfunction "2_2") (pintype "passive"))
    )
    (net (code "57") (name "MOTOR_B_FWD") (class "Default")
      (node (ref "IC9") (pin "4") (pinfunction "FIN_4") (pintype "input"))
      (node (ref "SV13") (pin "5") (pinfunction "5_5") (pintype "passive"))
    )
    (net (code "58") (name "MOTOR_B_REV") (class "Default")
      (node (ref "IC9") (pin "5") (pinfunction "RIN_5") (pintype "input"))
      (node (ref "SV13") (pin "6") (pinfunction "6_6") (pintype "passive"))
    )
    (net (code "59") (name "MOTOR_B_VREF") (class "Default")
      (node (ref "IC9") (pin "6") (pinfunction "VREF_6") (pintype "passive"))
      (node (ref "R14") (pin "2") (pinfunction "2_2") (pintype "passive"))
    )
    (net (code "60") (name "Net-(D13-PadA)") (class "Default")
      (node (ref "D13") (pin "A") (pinfunction "A_A") (pintype "passive"))
      (node (ref "JP8") (pin "1") (pinfunction "1_1") (pintype "passive"))
    )
    (net (code "61") (name "Net-(D13-PadC)") (class "Default")
      (node (ref "D13") (pin "C") (pinfunction "C_C") (pintype "passive"))
      (node (ref "U$7") (pin "COM") (pinfunction "COM_COM") (pintype "bidirectional"))
    )
    (net (code "62") (name "Net-(IC2-O1)") (class "Default")
      (node (ref "D6") (pin "C") (pinfunction "C_C") (pintype "passive"))
      (node (ref "IC2") (pin "16") (pinfunction "O1_16") (pintype "open_collector"))
    )
    (net (code "63") (name "Net-(IC2-O2)") (class "Default")
      (node (ref "D5") (pin "C") (pinfunction "C_C") (pintype "passive"))
      (node (ref "IC2") (pin "15") (pinfunction "O2_15") (pintype "open_collector"))
    )
    (net (code "64") (name "Net-(IC2-O3)") (class "Default")
      (node (ref "D4") (pin "C") (pinfunction "C_C") (pintype "passive"))
      (node (ref "IC2") (pin "14") (pinfunction "O3_14") (pintype "open_collector"))
    )
    (net (code "65") (name "Net-(IC2-O4)") (class "Default")
      (node (ref "D3") (pin "C") (pinfunction "C_C") (pintype "passive"))
      (node (ref "IC2") (pin "13") (pinfunction "O4_13") (pintype "open_collector"))
    )
    (net (code "66") (name "Net-(IC2-O5)") (class "Default")
      (node (ref "D2") (pin "C") (pinfunction "C_C") (pintype "passive"))
      (node (ref "IC2") (pin "12") (pinfunction "O5_12") (pintype "open_collector"))
    )
    (net (code "67") (name "Net-(IC2-O6)") (class "Default")
      (node (ref "D1") (pin "C") (pinfunction "C_C") (pintype "passive"))
      (node (ref "IC2") (pin "11") (pinfunction "O6_11") (pintype "open_collector"))
    )
    (net (code "68") (name "Net-(IC4-O1)") (class "Default")
      (node (ref "D12") (pin "C") (pinfunction "C_C") (pintype "passive"))
      (node (ref "IC4") (pin "16") (pinfunction "O1_16") (pintype "open_collector"))
    )
    (net (code "69") (name "Net-(IC4-O2)") (class "Default")
      (node (ref "D11") (pin "C") (pinfunction "C_C") (pintype "passive"))
      (node (ref "IC4") (pin "15") (pinfunction "O2_15") (pintype "open_collector"))
    )
    (net (code "70") (name "Net-(IC4-O3)") (class "Default")
      (node (ref "D10") (pin "C") (pinfunction "C_C") (pintype "passive"))
      (node (ref "IC4") (pin "14") (pinfunction "O3_14") (pintype "open_collector"))
    )
    (net (code "71") (name "Net-(IC4-O4)") (class "Default")
      (node (ref "D9") (pin "C") (pinfunction "C_C") (pintype "passive"))
      (node (ref "IC4") (pin "13") (pinfunction "O4_13") (pintype "open_collector"))
    )
    (net (code "72") (name "Net-(IC4-O5)") (class "Default")
      (node (ref "D8") (pin "C") (pinfunction "C_C") (pintype "passive"))
      (node (ref "IC4") (pin "12") (pinfunction "O5_12") (pintype "open_collector"))
    )
    (net (code "73") (name "Net-(IC4-O6)") (class "Default")
      (node (ref "D7") (pin "C") (pinfunction "C_C") (pintype "passive"))
      (node (ref "IC4") (pin "11") (pinfunction "O6_11") (pintype "open_collector"))
    )
    (net (code "74") (name "Net-(IC5-O1)") (class "Default")
      (node (ref "D20") (pin "C") (pinfunction "C_C") (pintype "passive"))
      (node (ref "IC5") (pin "16") (pinfunction "O1_16") (pintype "open_collector"))
    )
    (net (code "75") (name "Net-(IC5-O2)") (class "Default")
      (node (ref "D19") (pin "C") (pinfunction "C_C") (pintype "passive"))
      (node (ref "IC5") (pin "15") (pinfunction "O2_15") (pintype "open_collector"))
    )
    (net (code "76") (name "Net-(IC5-O3)") (class "Default")
      (node (ref "D18") (pin "C") (pinfunction "C_C") (pintype "passive"))
      (node (ref "IC5") (pin "14") (pinfunction "O3_14") (pintype "open_collector"))
    )
    (net (code "77") (name "Net-(IC5-O4)") (class "Default")
      (node (ref "D17") (pin "C") (pinfunction "C_C") (pintype "passive"))
      (node (ref "IC5") (pin "13") (pinfunction "O4_13") (pintype "open_collector"))
    )
    (net (code "78") (name "Net-(IC5-O5)") (class "Default")
      (node (ref "D16") (pin "C") (pinfunction "C_C") (pintype "passive"))
      (node (ref "IC5") (pin "12") (pinfunction "O5_12") (pintype "open_collector"))
    )
    (net (code "79") (name "Net-(IC5-O6)") (class "Default")
      (node (ref "D15") (pin "C") (pinfunction "C_C") (pintype "passive"))
      (node (ref "IC5") (pin "11") (pinfunction "O6_11") (pintype "open_collector"))
    )
    (net (code "80") (name "Net-(IC6-O1)") (class "Default")
      (node (ref "D26") (pin "C") (pinfunction "C_C") (pintype "passive"))
      (node (ref "IC6") (pin "16") (pinfunction "O1_16") (pintype "open_collector"))
    )
    (net (code "81") (name "Net-(IC6-O2)") (class "Default")
      (node (ref "D25") (pin "C") (pinfunction "C_C") (pintype "passive"))
      (node (ref "IC6") (pin "15") (pinfunction "O2_15") (pintype "open_collector"))
    )
    (net (code "82") (name "Net-(IC6-O3)") (class "Default")
      (node (ref "D24") (pin "C") (pinfunction "C_C") (pintype "passive"))
      (node (ref "IC6") (pin "14") (pinfunction "O3_14") (pintype "open_collector"))
    )
    (net (code "83") (name "Net-(IC6-O4)") (class "Default")
      (node (ref "D23") (pin "C") (pinfunction "C_C") (pintype "passive"))
      (node (ref "IC6") (pin "13") (pinfunction "O4_13") (pintype "open_collector"))
    )
    (net (code "84") (name "Net-(IC6-O5)") (class "Default")
      (node (ref "D22") (pin "C") (pinfunction "C_C") (pintype "passive"))
      (node (ref "IC6") (pin "12") (pinfunction "O5_12") (pintype "open_collector"))
    )
    (net (code "85") (name "Net-(IC6-O6)") (class "Default")
      (node (ref "D21") (pin "C") (pinfunction "C_C") (pintype "passive"))
      (node (ref "IC6") (pin "11") (pinfunction "O6_11") (pintype "open_collector"))
    )
    (net (code "86") (name "Net-(IC7-O1)") (class "Default")
      (node (ref "IC7") (pin "16") (pinfunction "O1_16") (pintype "open_collector"))
      (node (ref "LED_E") (pin "K") (pinfunction "C_K") (pintype "passive"))
    )
    (net (code "87") (name "Net-(IC7-O2)") (class "Default")
      (node (ref "IC7") (pin "15") (pinfunction "O2_15") (pintype "open_collector"))
      (node (ref "LED_F") (pin "K") (pinfunction "C_K") (pintype "passive"))
    )
    (net (code "88") (name "Net-(IC7-O3)") (class "Default")
      (node (ref "IC7") (pin "14") (pinfunction "O3_14") (pintype "open_collector"))
      (node (ref "LED_G") (pin "K") (pinfunction "C_K") (pintype "passive"))
    )
    (net (code "89") (name "Net-(IC7-O4)") (class "Default")
      (node (ref "IC7") (pin "13") (pinfunction "O4_13") (pintype "open_collector"))
      (node (ref "LED_H") (pin "K") (pinfunction "C_K") (pintype "passive"))
    )
    (net (code "90") (name "Net-(IC8-OUT1)") (class "Default")
      (node (ref "IC8") (pin "1") (pinfunction "OUT1_1") (pintype "output"))
      (node (ref "U$1") (pin "P$2") (pinfunction "P$2_P$2") (pintype "bidirectional"))
    )
    (net (code "91") (name "Net-(IC8-OUT2)") (class "Default")
      (node (ref "IC8") (pin "7") (pinfunction "OUT2_7") (pintype "output"))
      (node (ref "U$1") (pin "P$1") (pinfunction "P$1_P$1") (pintype "bidirectional"))
    )
    (net (code "92") (name "Net-(IC9-OUT1)") (class "Default")
      (node (ref "IC9") (pin "1") (pinfunction "OUT1_1") (pintype "output"))
      (node (ref "U$2") (pin "P$2") (pinfunction "P$2_P$2") (pintype "bidirectional"))
    )
    (net (code "93") (name "Net-(IC9-OUT2)") (class "Default")
      (node (ref "IC9") (pin "7") (pinfunction "OUT2_7") (pintype "output"))
      (node (ref "U$2") (pin "P$1") (pinfunction "P$1_P$1") (pintype "bidirectional"))
    )
    (net (code "94") (name "Net-(IC11A--IN)") (class "Default")
      (node (ref "IC11") (pin "10") (pinfunction "-IN_10") (pintype "input"))
      (node (ref "IC11") (pin "4") (pinfunction "-IN_4") (pintype "input"))
      (node (ref "IC11") (pin "6") (pinfunction "-IN_6") (pintype "input"))
      (node (ref "IC11") (pin "8") (pinfunction "-IN_8") (pintype "input"))
      (node (ref "IC12") (pin "10") (pinfunction "-IN_10") (pintype "input"))
      (node (ref "IC12") (pin "4") (pinfunction "-IN_4") (pintype "input"))
      (node (ref "IC12") (pin "6") (pinfunction "-IN_6") (pintype "input"))
      (node (ref "IC12") (pin "8") (pinfunction "-IN_8") (pintype "input"))
      (node (ref "R12") (pin "2") (pinfunction "2_2") (pintype "passive"))
      (node (ref "R13") (pin "1") (pinfunction "1_1") (pintype "passive"))
    )
    (net (code "95") (name "Net-(LED_A-PadA)") (class "Default")
      (node (ref "LED_A") (pin "A") (pinfunction "A_A") (pintype "passive"))
      (node (ref "U$4") (pin "1") (pinfunction "1_1") (pintype "bidirectional"))
    )
    (net (code "96") (name "Net-(LED_B-PadA)") (class "Default")
      (node (ref "LED_B") (pin "A") (pinfunction "A_A") (pintype "passive"))
      (node (ref "U$4") (pin "2") (pinfunction "2_2") (pintype "bidirectional"))
    )
    (net (code "97") (name "Net-(LED_C-PadA)") (class "Default")
      (node (ref "LED_C") (pin "A") (pinfunction "A_A") (pintype "passive"))
      (node (ref "U$4") (pin "3") (pinfunction "3_3") (pintype "bidirectional"))
    )
    (net (code "98") (name "Net-(LED_D-PadA)") (class "Default")
      (node (ref "LED_D") (pin "A") (pinfunction "A_A") (pintype "passive"))
      (node (ref "U$4") (pin "4") (pinfunction "4_4") (pintype "bidirectional"))
    )
    (net (code "99") (name "Net-(LED_E-PadA)") (class "Default")
      (node (ref "LED_E") (pin "A") (pinfunction "A_A") (pintype "passive"))
      (node (ref "U$4") (pin "6") (pinfunction "6_6") (pintype "bidirectional"))
    )
    (net (code "100") (name "Net-(LED_F-PadA)") (class "Default")
      (node (ref "LED_F") (pin "A") (pinfunction "A_A") (pintype "passive"))
      (node (ref "U$4") (pin "7") (pinfunction "7_7") (pintype "bidirectional"))
    )
    (net (code "101") (name "Net-(LED_G-PadA)") (class "Default")
      (node (ref "LED_G") (pin "A") (pinfunction "A_A") (pintype "passive"))
      (node (ref "U$4") (pin "8") (pinfunction "8_8") (pintype "bidirectional"))
    )
    (net (code "102") (name "Net-(LED_H-PadA)") (class "Default")
      (node (ref "LED_H") (pin "A") (pinfunction "A_A") (pintype "passive"))
      (node (ref "U$4") (pin "9") (pinfunction "9_9") (pintype "bidirectional"))
    )
    (net (code "103") (name "Net-(R11-Pad1)") (class "Default")
      (node (ref "R11") (pin "1") (pinfunction "1_1") (pintype "passive"))
      (node (ref "R8") (pin "2") (pinfunction "2_2") (pintype "passive"))
    )
    (net (code "104") (name "Net-(R14-Pad1)") (class "Default")
      (node (ref "R14") (pin "1") (pinfunction "1_1") (pintype "passive"))
      (node (ref "R9") (pin "2") (pinfunction "2_2") (pintype "passive"))
    )
    (net (code "105") (name "Net-(R15-Pad1)") (class "Default")
      (node (ref "R15") (pin "1") (pinfunction "1_1") (pintype "passive"))
      (node (ref "SV14") (pin "4") (pinfunction "4_4") (pintype "passive"))
      (node (ref "SV14") (pin "5") (pinfunction "5_5") (pintype "passive"))
      (node (ref "SV14") (pin "6") (pinfunction "6_6") (pintype "passive"))
    )
    (net (code "106") (name "Net-(R16-Pad1)") (class "Default")
      (node (ref "R16") (pin "1") (pinfunction "1_1") (pintype "passive"))
      (node (ref "SV15") (pin "4") (pinfunction "4_4") (pintype "passive"))
      (node (ref "SV15") (pin "5") (pinfunction "5_5") (pintype "passive"))
      (node (ref "SV15") (pin "6") (pinfunction "6_6") (pintype "passive"))
    )
    (net (code "107") (name "OUTPUT_A_IN") (class "Default")
      (node (ref "IC7") (pin "6") (pinfunction "I6_6") (pintype "input"))
      (node (ref "SV13") (pin "4") (pinfunction "4_4") (pintype "passive"))
    )
    (net (code "108") (name "OUTPUT_A_OUT") (class "Default")
      (node (ref "IC7") (pin "11") (pinfunction "O6_11") (pintype "open_collector"))
      (node (ref "JP1") (pin "1") (pinfunction "1_1") (pintype "passive"))
    )
    (net (code "109") (name "OUTPUT_B_IN") (class "Default")
      (node (ref "IC7") (pin "5") (pinfunction "I5_5") (pintype "input"))
      (node (ref "SV13") (pin "3") (pinfunction "3_3") (pintype "passive"))
    )
    (net (code "110") (name "OUTPUT_B_OUT") (class "Default")
      (node (ref "IC7") (pin "12") (pinfunction "O5_12") (pintype "open_collector"))
      (node (ref "JP2") (pin "1") (pinfunction "1_1") (pintype "passive"))
    )
    (net (code "111") (name "RES_D1") (class "Default")
      (node (ref "D1") (pin "A") (pinfunction "A_A") (pintype "passive"))
      (node (ref "U$19") (pin "6") (pinfunction "6_6") (pintype "bidirectional"))
    )
    (net (code "112") (name "RES_D2") (class "Default")
      (node (ref "D2") (pin "A") (pinfunction "A_A") (pintype "passive"))
      (node (ref "U$19") (pin "7") (pinfunction "7_7") (pintype "bidirectional"))
    )
    (net (code "113") (name "RES_D3") (class "Default")
      (node (ref "D3") (pin "A") (pinfunction "A_A") (pintype "passive"))
      (node (ref "U$19") (pin "8") (pinfunction "8_8") (pintype "bidirectional"))
    )
    (net (code "114") (name "RES_D4") (class "Default")
      (node (ref "D4") (pin "A") (pinfunction "A_A") (pintype "passive"))
      (node (ref "U$19") (pin "1") (pinfunction "1_1") (pintype "bidirectional"))
    )
    (net (code "115") (name "RES_D5") (class "Default")
      (node (ref "D5") (pin "A") (pinfunction "A_A") (pintype "passive"))
      (node (ref "U$19") (pin "2") (pinfunction "2_2") (pintype "bidirectional"))
    )
    (net (code "116") (name "RES_D6") (class "Default")
      (node (ref "D6") (pin "A") (pinfunction "A_A") (pintype "passive"))
      (node (ref "U$19") (pin "3") (pinfunction "3_3") (pintype "bidirectional"))
    )
    (net (code "117") (name "RES_D7") (class "Default")
      (node (ref "D7") (pin "A") (pinfunction "A_A") (pintype "passive"))
      (node (ref "U$5") (pin "6") (pinfunction "6_6") (pintype "bidirectional"))
    )
    (net (code "118") (name "RES_D8") (class "Default")
      (node (ref "D8") (pin "A") (pinfunction "A_A") (pintype "passive"))
      (node (ref "U$5") (pin "7") (pinfunction "7_7") (pintype "bidirectional"))
    )
    (net (code "119") (name "RES_D9") (class "Default")
      (node (ref "D9") (pin "A") (pinfunction "A_A") (pintype "passive"))
      (node (ref "U$5") (pin "8") (pinfunction "8_8") (pintype "bidirectional"))
    )
    (net (code "120") (name "RES_D10") (class "Default")
      (node (ref "D10") (pin "A") (pinfunction "A_A") (pintype "passive"))
      (node (ref "U$5") (pin "1") (pinfunction "1_1") (pintype "bidirectional"))
    )
    (net (code "121") (name "RES_D11") (class "Default")
      (node (ref "D11") (pin "A") (pinfunction "A_A") (pintype "passive"))
      (node (ref "U$5") (pin "2") (pinfunction "2_2") (pintype "bidirectional"))
    )
    (net (code "122") (name "RES_D12") (class "Default")
      (node (ref "D12") (pin "A") (pinfunction "A_A") (pintype "passive"))
      (node (ref "U$5") (pin "3") (pinfunction "3_3") (pintype "bidirectional"))
    )
    (net (code "123") (name "RES_D15") (class "Default")
      (node (ref "D15") (pin "A") (pinfunction "A_A") (pintype "passive"))
      (node (ref "U$6") (pin "6") (pinfunction "6_6") (pintype "bidirectional"))
    )
    (net (code "124") (name "RES_D16") (class "Default")
      (node (ref "D16") (pin "A") (pinfunction "A_A") (pintype "passive"))
      (node (ref "U$6") (pin "7") (pinfunction "7_7") (pintype "bidirectional"))
    )
    (net (code "125") (name "RES_D17") (class "Default")
      (node (ref "D17") (pin "A") (pinfunction "A_A") (pintype "passive"))
      (node (ref "U$6") (pin "8") (pinfunction "8_8") (pintype "bidirectional"))
    )
    (net (code "126") (name "RES_D18") (class "Default")
      (node (ref "D18") (pin "A") (pinfunction "A_A") (pintype "passive"))
      (node (ref "U$6") (pin "1") (pinfunction "1_1") (pintype "bidirectional"))
    )
    (net (code "127") (name "RES_D19") (class "Default")
      (node (ref "D19") (pin "A") (pinfunction "A_A") (pintype "passive"))
      (node (ref "U$6") (pin "2") (pinfunction "2_2") (pintype "bidirectional"))
    )
    (net (code "128") (name "RES_D20") (class "Default")
      (node (ref "D20") (pin "A") (pinfunction "A_A") (pintype "passive"))
      (node (ref "U$6") (pin "3") (pinfunction "3_3") (pintype "bidirectional"))
    )
    (net (code "129") (name "RES_D21") (class "Default")
      (node (ref "D21") (pin "A") (pinfunction "A_A") (pintype "passive"))
      (node (ref "U$9") (pin "6") (pinfunction "6_6") (pintype "bidirectional"))
    )
    (net (code "130") (name "RES_D22") (class "Default")
      (node (ref "D22") (pin "A") (pinfunction "A_A") (pintype "passive"))
      (node (ref "U$9") (pin "7") (pinfunction "7_7") (pintype "bidirectional"))
    )
    (net (code "131") (name "RES_D23") (class "Default")
      (node (ref "D23") (pin "A") (pinfunction "A_A") (pintype "passive"))
      (node (ref "U$9") (pin "8") (pinfunction "8_8") (pintype "bidirectional"))
    )
    (net (code "132") (name "RES_D24") (class "Default")
      (node (ref "D24") (pin "A") (pinfunction "A_A") (pintype "passive"))
      (node (ref "U$9") (pin "1") (pinfunction "1_1") (pintype "bidirectional"))
    )
    (net (code "133") (name "RES_D25") (class "Default")
      (node (ref "D25") (pin "A") (pinfunction "A_A") (pintype "passive"))
      (node (ref "U$9") (pin "2") (pinfunction "2_2") (pintype "bidirectional"))
    )
    (net (code "134") (name "RES_D26") (class "Default")
      (node (ref "D26") (pin "A") (pinfunction "A_A") (pintype "passive"))
      (node (ref "U$9") (pin "3") (pinfunction "3_3") (pintype "bidirectional"))
    )
    (net (code "135") (name "VDD") (class "Default")
      (node (ref "C2") (pin "2") (pinfunction "2_2") (pintype "passive"))
      (node (ref "C4") (pin "1") (pinfunction "1_1") (pintype "passive"))
      (node (ref "C6") (pin "1") (pinfunction "1_1") (pintype "passive"))
      (node (ref "IC1") (pin "14") (pinfunction "VDD_14") (pintype "power_in"))
      (node (ref "IC10") (pin "2") (pinfunction "VOUT_2") (pintype "output"))
      (node (ref "IC11") (pin "3") (pinfunction "V+_3") (pintype "power_in"))
      (node (ref "IC12") (pin "3") (pinfunction "V+_3") (pintype "power_in"))
      (node (ref "IC2") (pin "9") (pinfunction "CD+_9") (pintype "passive"))
      (node (ref "IC3") (pin "14") (pinfunction "VDD_14") (pintype "power_in"))
      (node (ref "IC4") (pin "9") (pinfunction "CD+_9") (pintype "passive"))
      (node (ref "IC5") (pin "9") (pinfunction "CD+_9") (pintype "passive"))
      (node (ref "IC6") (pin "9") (pinfunction "CD+_9") (pintype "passive"))
      (node (ref "IC7") (pin "9") (pinfunction "CD+_9") (pintype "passive"))
      (node (ref "IC8") (pin "3") (pinfunction "VCC_3") (pintype "power_in"))
      (node (ref "IC9") (pin "3") (pinfunction "VCC_3") (pintype "power_in"))
      (node (ref "JP1") (pin "2") (pinfunction "2_2") (pintype "passive"))
      (node (ref "JP2") (pin "2") (pinfunction "2_2") (pintype "passive"))
      (node (ref "PH1") (pin "1") (pinfunction "1_1") (pintype "passive"))
      (node (ref "PH2") (pin "1") (pinfunction "1_1") (pintype "passive"))
      (node (ref "PH3") (pin "1") (pinfunction "1_1") (pintype "passive"))
      (node (ref "PH4") (pin "1") (pinfunction "1_1") (pintype "passive"))
      (node (ref "PH5") (pin "1") (pinfunction "1_1") (pintype "passive"))
      (node (ref "PH6") (pin "1") (pinfunction "1_1") (pintype "passive"))
      (node (ref "PH7") (pin "1") (pinfunction "1_1") (pintype "passive"))
      (node (ref "PH8") (pin "1") (pinfunction "1_1") (pintype "passive"))
      (node (ref "R12") (pin "1") (pinfunction "1_1") (pintype "passive"))
      (node (ref "R8") (pin "1") (pinfunction "1_1") (pintype "passive"))
      (node (ref "R9") (pin "1") (pinfunction "1_1") (pintype "passive"))
      (node (ref "SV10") (pin "1") (pinfunction "1_1") (pintype "passive"))
      (node (ref "SV10") (pin "6") (pinfunction "6_6") (pintype "passive"))
      (node (ref "SV11") (pin "1") (pinfunction "1_1") (pintype "passive"))
      (node (ref "SV11") (pin "6") (pinfunction "6_6") (pintype "passive"))
      (node (ref "SV12") (pin "1") (pinfunction "1_1") (pintype "passive"))
      (node (ref "SV12") (pin "6") (pinfunction "6_6") (pintype "passive"))
      (node (ref "SV14") (pin "1") (pinfunction "1_1") (pintype "passive"))
      (node (ref "SV14") (pin "2") (pinfunction "2_2") (pintype "passive"))
      (node (ref "SV14") (pin "3") (pinfunction "3_3") (pintype "passive"))
      (node (ref "SV15") (pin "1") (pinfunction "1_1") (pintype "passive"))
      (node (ref "SV15") (pin "2") (pinfunction "2_2") (pintype "passive"))
      (node (ref "SV15") (pin "3") (pinfunction "3_3") (pintype "passive"))
      (node (ref "SV9") (pin "1") (pinfunction "1_1") (pintype "passive"))
      (node (ref "SV9") (pin "6") (pinfunction "6_6") (pintype "passive"))
      (node (ref "U$10") (pin "10") (pinfunction "10_10") (pintype "bidirectional"))
      (node (ref "U$10") (pin "5") (pinfunction "5_5") (pintype "bidirectional"))
      (node (ref "U$11") (pin "10") (pinfunction "10_10") (pintype "bidirectional"))
      (node (ref "U$11") (pin "5") (pinfunction "5_5") (pintype "bidirectional"))
      (node (ref "U$19") (pin "10") (pinfunction "10_10") (pintype "bidirectional"))
      (node (ref "U$19") (pin "5") (pinfunction "5_5") (pintype "bidirectional"))
      (node (ref "U$20") (pin "10") (pinfunction "10_10") (pintype "bidirectional"))
      (node (ref "U$20") (pin "5") (pinfunction "5_5") (pintype "bidirectional"))
      (node (ref "U$3") (pin "10") (pinfunction "10_10") (pintype "bidirectional"))
      (node (ref "U$3") (pin "5") (pinfunction "5_5") (pintype "bidirectional"))
      (node (ref "U$4") (pin "10") (pinfunction "10_10") (pintype "bidirectional"))
      (node (ref "U$4") (pin "5") (pinfunction "5_5") (pintype "bidirectional"))
      (node (ref "U$5") (pin "10") (pinfunction "10_10") (pintype "bidirectional"))
      (node (ref "U$5") (pin "5") (pinfunction "5_5") (pintype "bidirectional"))
      (node (ref "U$6") (pin "10") (pinfunction "10_10") (pintype "bidirectional"))
      (node (ref "U$6") (pin "5") (pinfunction "5_5") (pintype "bidirectional"))
      (node (ref "U$9") (pin "10") (pinfunction "10_10") (pintype "bidirectional"))
      (node (ref "U$9") (pin "5") (pinfunction "5_5") (pintype "bidirectional"))
    )
    (net (code "136") (name "VIN") (class "Default")
      (node (ref "C1") (pin "2") (pinfunction "2_2") (pintype "passive"))
      (node (ref "C3") (pin "1") (pinfunction "1_1") (pintype "passive"))
      (node (ref "C5") (pin "1") (pinfunction "1_1") (pintype "passive"))
      (node (ref "IC10") (pin "3") (pinfunction "VIN_3") (pintype "input"))
      (node (ref "IC8") (pin "2") (pinfunction "VCC_2") (pintype "power_in"))
      (node (ref "IC9") (pin "2") (pinfunction "VCC_2") (pintype "power_in"))
      (node (ref "U$7") (pin "NC") (pinfunction "NC_NC") (pintype "bidirectional"))
    )
    (net (code "137") (name "unconnected-(IC7-I7-Pad7)") (class "Default")
      (node (ref "IC7") (pin "7") (pinfunction "I7_7") (pintype "input"))
    )
    (net (code "138") (name "unconnected-(IC7-O7-Pad10)") (class "Default")
      (node (ref "IC7") (pin "10") (pinfunction "O7_10") (pintype "open_collector"))
    )
    (net (code "139") (name "unconnected-(R1-Pad3)") (class "Default")
      (node (ref "R1") (pin "3") (pinfunction "3_3") (pintype "passive"))
    )
    (net (code "140") (name "unconnected-(R2-Pad3)") (class "Default")
      (node (ref "R2") (pin "3") (pinfunction "3_3") (pintype "passive"))
    )
    (net (code "141") (name "unconnected-(R3-Pad3)") (class "Default")
      (node (ref "R3") (pin "3") (pinfunction "3_3") (pintype "passive"))
    )
    (net (code "142") (name "unconnected-(R4-Pad3)") (class "Default")
      (node (ref "R4") (pin "3") (pinfunction "3_3") (pintype "passive"))
    )
    (net (code "143") (name "unconnected-(R5-Pad3)") (class "Default")
      (node (ref "R5") (pin "3") (pinfunction "3_3") (pintype "passive"))
    )
    (net (code "144") (name "unconnected-(R6-Pad3)") (class "Default")
      (node (ref "R6") (pin "3") (pinfunction "3_3") (pintype "passive"))
    )
    (net (code "145") (name "unconnected-(R7-Pad3)") (class "Default")
      (node (ref "R7") (pin "3") (pinfunction "3_3") (pintype "passive"))
    )
    (net (code "146") (name "unconnected-(R10-Pad3)") (class "Default")
      (node (ref "R10") (pin "3") (pinfunction "3_3") (pintype "passive"))
    )
    (net (code "147") (name "unconnected-(U$3-Pad4)") (class "Default")
      (node (ref "U$3") (pin "4") (pinfunction "4_4") (pintype "bidirectional"))
    )
    (net (code "148") (name "unconnected-(U$3-Pad9)") (class "Default")
      (node (ref "U$3") (pin "9") (pinfunction "9_9") (pintype "bidirectional"))
    )
    (net (code "149") (name "unconnected-(U$5-Pad4)") (class "Default")
      (node (ref "U$5") (pin "4") (pinfunction "4_4") (pintype "bidirectional"))
    )
    (net (code "150") (name "unconnected-(U$5-Pad9)") (class "Default")
      (node (ref "U$5") (pin "9") (pinfunction "9_9") (pintype "bidirectional"))
    )
    (net (code "151") (name "unconnected-(U$6-Pad4)") (class "Default")
      (node (ref "U$6") (pin "4") (pinfunction "4_4") (pintype "bidirectional"))
    )
    (net (code "152") (name "unconnected-(U$6-Pad9)") (class "Default")
      (node (ref "U$6") (pin "9") (pinfunction "9_9") (pintype "bidirectional"))
    )
    (net (code "153") (name "unconnected-(U$7-PadNO)") (class "Default")
      (node (ref "U$7") (pin "NO") (pinfunction "NO_NO") (pintype "bidirectional"))
    )
    (net (code "154") (name "unconnected-(U$9-Pad4)") (class "Default")
      (node (ref "U$9") (pin "4") (pinfunction "4_4") (pintype "bidirectional"))
    )
    (net (code "155") (name "unconnected-(U$9-Pad9)") (class "Default")
      (node (ref "U$9") (pin "9") (pinfunction "9_9") (pintype "bidirectional"))
    )
    (net (code "156") (name "unconnected-(U$10-Pad4)") (class "Default")
      (node (ref "U$10") (pin "4") (pinfunction "4_4") (pintype "bidirectional"))
    )
    (net (code "157") (name "unconnected-(U$10-Pad9)") (class "Default")
      (node (ref "U$10") (pin "9") (pinfunction "9_9") (pintype "bidirectional"))
    )
    (net (code "158") (name "unconnected-(U$11-Pad4)") (class "Default")
      (node (ref "U$11") (pin "4") (pinfunction "4_4") (pintype "bidirectional"))
    )
    (net (code "159") (name "unconnected-(U$11-Pad9)") (class "Default")
      (node (ref "U$11") (pin "9") (pinfunction "9_9") (pintype "bidirectional"))
    )
    (net (code "160") (name "unconnected-(U$19-Pad4)") (class "Default")
      (node (ref "U$19") (pin "4") (pinfunction "4_4") (pintype "bidirectional"))
    )
    (net (code "161") (name "unconnected-(U$19-Pad9)") (class "Default")
      (node (ref "U$19") (pin "9") (pinfunction "9_9") (pintype "bidirectional"))
    )
    (net (code "162") (name "unconnected-(U$20-Pad4)") (class "Default")
      (node (ref "U$20") (pin "4") (pinfunction "4_4") (pintype "bidirectional"))
    )
    (net (code "163") (name "unconnected-(U$20-Pad9)") (class "Default")
      (node (ref "U$20") (pin "9") (pinfunction "9_9") (pintype "bidirectional"))
    )
  )
)
